# PG11__CAN_CONN.net
KiCad netlist of a schematic drawn in Altium Designer
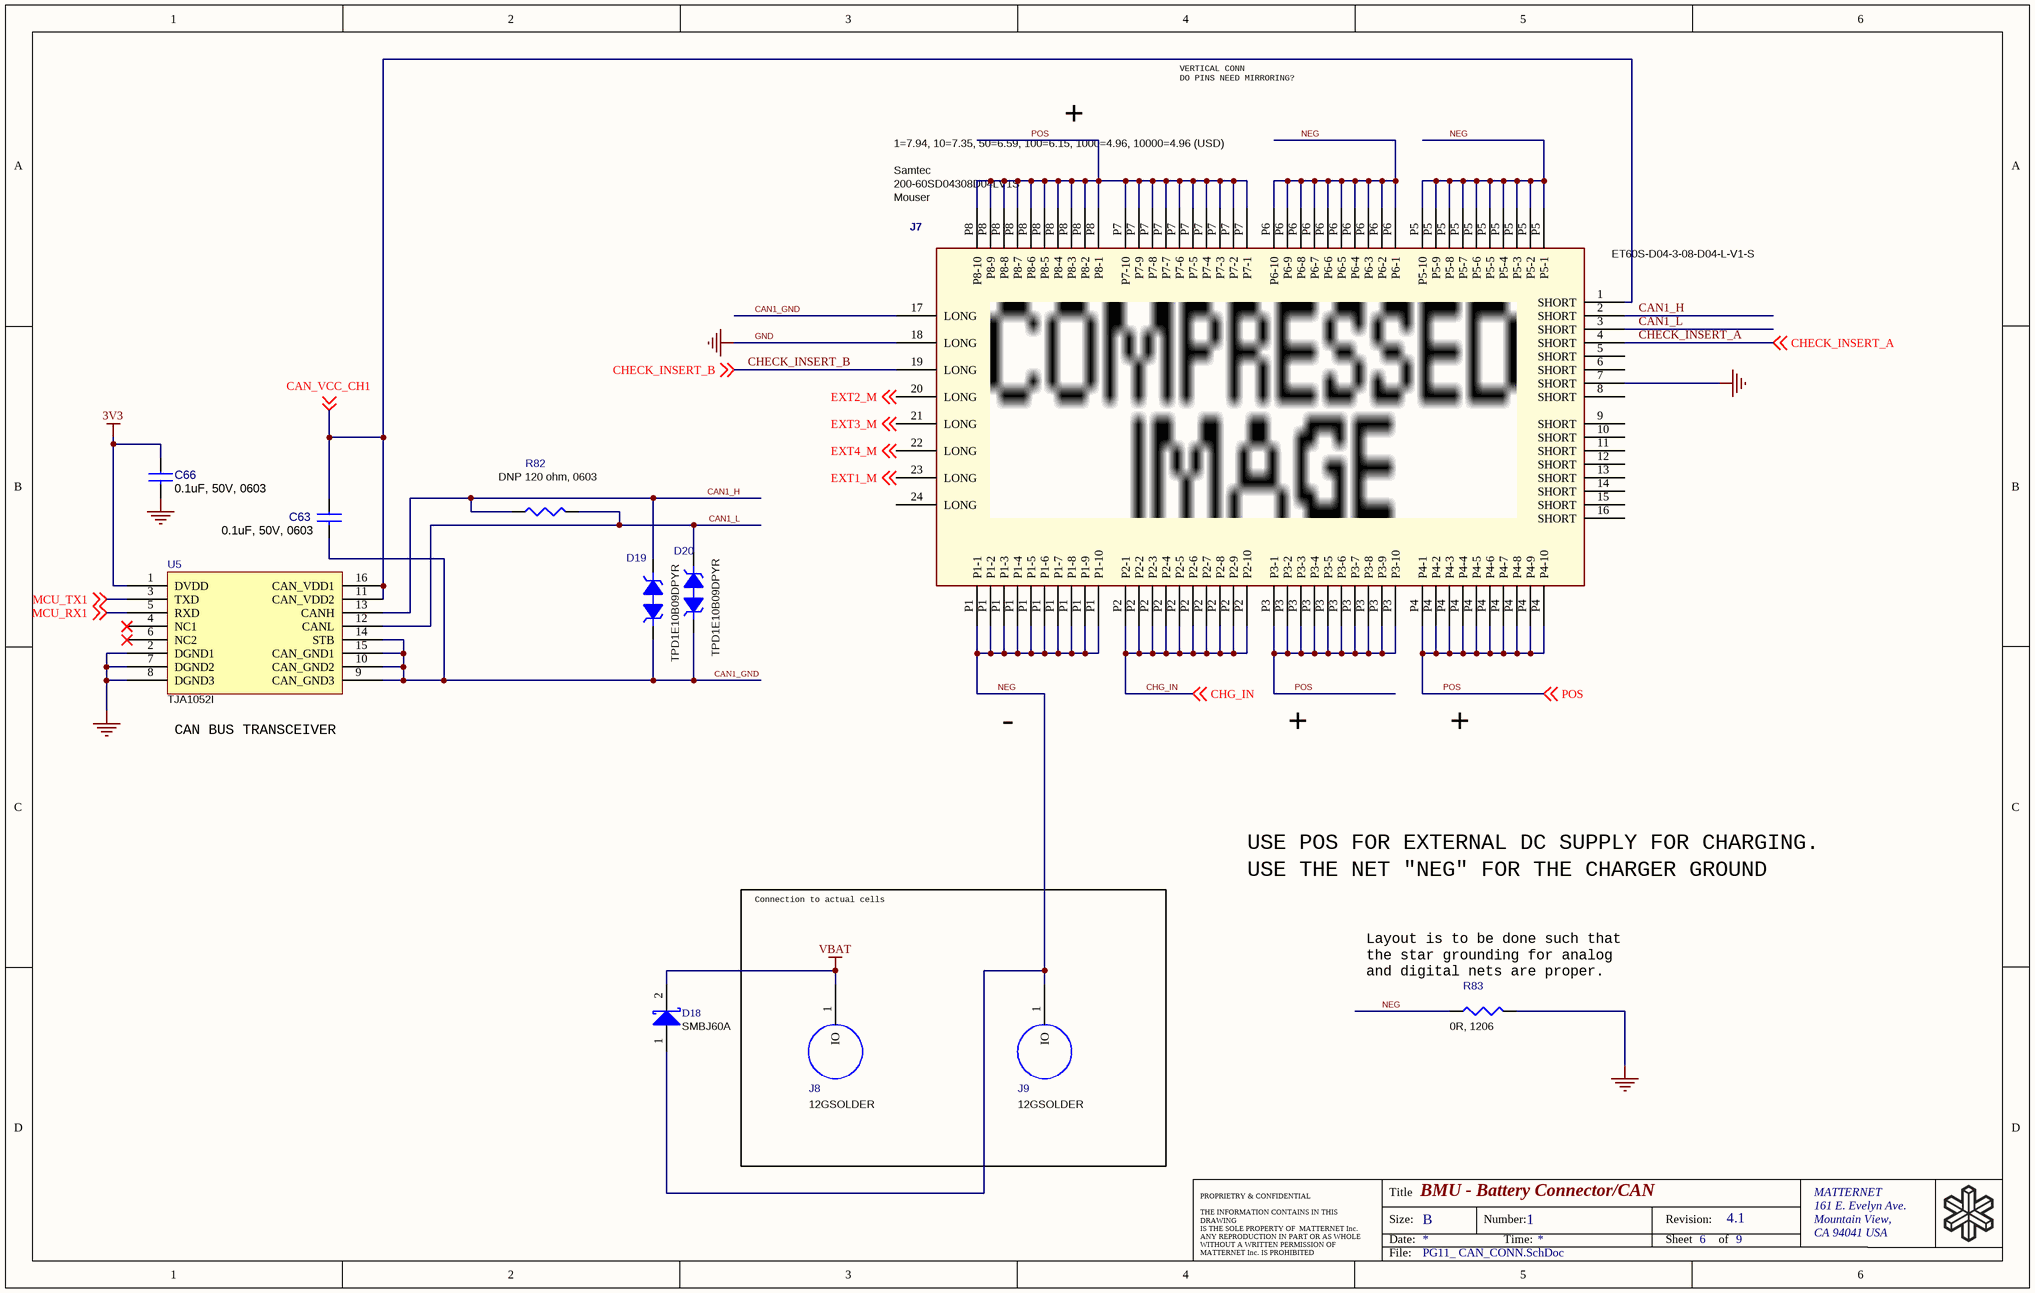
[diagram p0: PG11_ CAN_CONN.SchDoc]

(export (version "E")
  (design (tool "Eeschema 10.0.6"))
  (components
    (comp (ref "C63")
      (value "0.1uF, 50V, 0603")
      (footprint "C0603")
      (description "CAP CER 0.1UF 50V 10% X7R 0603")
      (fields
        (field (name "MANUFACTURER") "Murata")
        (field (name "MANUFACTURER PART NUMBER") "GCJ188R71E104KA12D")
      )
      (libsource (lib "*") (part "CAP-Generic-0603"))
    )
    (comp (ref "C66")
      (value "0.1uF, 50V, 0603")
      (footprint "C0603")
      (description "CAP CER 0.1UF 50V 10% X7R 0603")
      (fields
        (field (name "MANUFACTURER") "Murata")
        (field (name "MANUFACTURER PART NUMBER") "GCJ188R71E104KA12D")
      )
      (libsource (lib "*") (part "CAP-Generic-0603"))
    )
    (comp (ref "D18")
      (value "SMBJ60A")
      (footprint "DO-214AA")
      (description "ESD Suppressors / TVS Diodes 60Vr")
      (fields
        (field (name "MANUFACTURER") "Vishay Semiconductors")
        (field (name "MANUFACTURER PART NUMBER") "SMBJ60A-E3/52")
      )
      (libsource (lib "M2_V8_BMU_V1.0") (part "SMBJ60A"))
    )
    (comp (ref "D19")
      (value "TPD1E10B09DPYR")
      (footprint "2X2SON")
      (description "TVS DIODE 9VWM 20VC 2X2SON")
      (fields (field (name "MANUFACTURER") "Texas Instruments"))
      (libsource (lib "*") (part "ESD BI-DIR TRIG 9VDC 0402_0"))
    )
    (comp (ref "D20")
      (value "TPD1E10B09DPYR")
      (footprint "2X2SON")
      (description "TVS DIODE 9VWM 20VC 2X2SON")
      (fields (field (name "MANUFACTURER") "Texas Instruments"))
      (libsource (lib "*") (part "ESD BI-DIR TRIG 9VDC 0402_0"))
    )
    (comp (ref "J7")
      (value "ET60S-D04-3-08-D04-L-V1-S")
      (footprint "ET60S-D04-3-08-D04-L-V1-S")
      (description "EXtreme Ten60 Power Connector")
      (fields
        (field (name "SUPPLIER 1") "Mouser")
        (field (name "SUPPLIER PART NUMBER 1") "200-60SD04308D04LV1S")
        (field (name "MANUFACTURER") "Samtec")
        (field (name "PRICING 1") "1=7.94, 10=7.35, 50=6.59, 100=6.15, 1000=4.96, 10000=4.96 (USD)")
      )
      (libsource (lib "M2_V8_BMU_V1.0") (part "ET60S-D04-3-08-D04-L-V1-S"))
    )
    (comp (ref "J8") (value "12GSOLDER") (footprint "12GPAD") (libsource (lib "*") (part "12GSOLDER")))
    (comp (ref "J9") (value "12GSOLDER") (footprint "12GPAD") (libsource (lib "*") (part "12GSOLDER")))
    (comp (ref "R82")
      (value "DNP 120 ohm, 0603")
      (footprint "R0603")
      (libsource (lib "*") (part "R-Generic-0603"))
    )
    (comp (ref "R83")
      (value "0R, 1206")
      (footprint "R1206")
      (description "RES SMD 0 OHM JUMPER 1/4W 1206")
      (fields
        (field (name "MANUFACTURER") "Yageo")
        (field (name "MANUFACTURER PART NUMBER") "RC1206JR-070RL")
      )
      (libsource (lib "*") (part "R-Generic-1206"))
    )
    (comp (ref "U5")
      (value "TJA1052I")
      (footprint "16-SOIC")
      (description "CAN Bus, Transceiver SOIC")
      (fields
        (field (name "MANUFACTURER") "NXP Semiconductors")
        (field (name "MANUFACTURER PART NUMBER") "TJA1052IT/5Y")
      )
      (libsource (lib "M2_V8_BMU_V1.0") (part "TJA1052I"))
    )
  )
  (nets
    (net (code "1") (name "/CAN1_GND") (class "Default")
      (node (ref "C63") (pin "2") (pinfunction "2_2") (pintype "passive"))
      (node (ref "D19") (pin "1") (pinfunction "1_1") (pintype "passive"))
      (node (ref "D20") (pin "1") (pinfunction "1_1") (pintype "passive"))
      (node (ref "J7") (pin "17") (pinfunction "LONG_17") (pintype "passive"))
      (node (ref "U5") (pin "10") (pinfunction "CAN_GND2_10") (pintype "passive"))
      (node (ref "U5") (pin "14") (pinfunction "STB_14") (pintype "passive"))
      (node (ref "U5") (pin "15") (pinfunction "CAN_GND1_15") (pintype "passive"))
      (node (ref "U5") (pin "9") (pinfunction "CAN_GND3_9") (pintype "passive"))
    )
    (net (code "2") (name "/CAN1_H") (class "Default")
      (node (ref "D19") (pin "2") (pinfunction "2_2") (pintype "passive"))
      (node (ref "J7") (pin "2") (pinfunction "SHORT_2") (pintype "passive"))
      (node (ref "R82") (pin "1") (pinfunction "1_1") (pintype "passive"))
      (node (ref "U5") (pin "13") (pinfunction "CANH_13") (pintype "passive"))
    )
    (net (code "3") (name "/CAN1_L") (class "Default")
      (node (ref "D20") (pin "2") (pinfunction "2_2") (pintype "passive"))
      (node (ref "J7") (pin "3") (pinfunction "SHORT_3") (pintype "passive"))
      (node (ref "R82") (pin "2") (pinfunction "2_2") (pintype "passive"))
      (node (ref "U5") (pin "12") (pinfunction "CANL_12") (pintype "passive"))
    )
    (net (code "4") (name "/NEG") (class "Default")
      (node (ref "D18") (pin "1") (pinfunction "A_1") (pintype "passive"))
      (node (ref "J7") (pin "P1") (pinfunction "P1-6_P1") (pintype "passive"))
      (node (ref "J7") (pin "P5") (pinfunction "P5-10_P5") (pintype "passive"))
      (node (ref "J7") (pin "P6") (pinfunction "P6-1_P6") (pintype "passive"))
      (node (ref "J9") (pin "1") (pinfunction "IO_1") (pintype "passive"))
      (node (ref "R83") (pin "2") (pinfunction "2_2") (pintype "passive"))
    )
    (net (code "5") (name "3V3") (class "Default")
      (node (ref "C66") (pin "1") (pinfunction "1_1") (pintype "passive"))
      (node (ref "U5") (pin "1") (pinfunction "DVDD_1") (pintype "passive"))
    )
    (net (code "6") (name "CAN_VCC_CH1") (class "Default")
      (node (ref "C63") (pin "1") (pinfunction "1_1") (pintype "passive"))
      (node (ref "J7") (pin "1") (pinfunction "SHORT_1") (pintype "passive"))
      (node (ref "U5") (pin "11") (pinfunction "CAN_VDD2_11") (pintype "passive"))
      (node (ref "U5") (pin "16") (pinfunction "CAN_VDD1_16") (pintype "passive"))
    )
    (net (code "7") (name "CHECK_INSERT_A") (class "Default")
      (node (ref "J7") (pin "4") (pinfunction "SHORT_4") (pintype "passive"))
    )
    (net (code "8") (name "CHECK_INSERT_B") (class "Default")
      (node (ref "J7") (pin "19") (pinfunction "LONG_19") (pintype "passive"))
    )
    (net (code "9") (name "CHG_IN") (class "Default")
      (node (ref "J7") (pin "P2") (pinfunction "P2-1_P2") (pintype "passive"))
    )
    (net (code "10") (name "EXT1_M") (class "Default")
      (node (ref "J7") (pin "23") (pinfunction "LONG_23") (pintype "passive"))
    )
    (net (code "11") (name "EXT2_M") (class "Default")
      (node (ref "J7") (pin "20") (pinfunction "LONG_20") (pintype "passive"))
    )
    (net (code "12") (name "EXT3_M") (class "Default")
      (node (ref "J7") (pin "21") (pinfunction "LONG_21") (pintype "passive"))
    )
    (net (code "13") (name "EXT4_M") (class "Default")
      (node (ref "J7") (pin "22") (pinfunction "LONG_22") (pintype "passive"))
    )
    (net (code "14") (name "GND") (class "Default")
      (node (ref "C66") (pin "2") (pinfunction "2_2") (pintype "passive"))
      (node (ref "J7") (pin "18") (pinfunction "LONG_18") (pintype "passive"))
      (node (ref "J7") (pin "7") (pinfunction "SHORT_7") (pintype "passive"))
      (node (ref "R83") (pin "1") (pinfunction "1_1") (pintype "passive"))
      (node (ref "U5") (pin "2") (pinfunction "DGND1_2") (pintype "passive"))
      (node (ref "U5") (pin "7") (pinfunction "DGND2_7") (pintype "passive"))
      (node (ref "U5") (pin "8") (pinfunction "DGND3_8") (pintype "passive"))
    )
    (net (code "15") (name "MCU_RX1") (class "Default")
      (node (ref "U5") (pin "5") (pinfunction "RXD_5") (pintype "passive"))
    )
    (net (code "16") (name "MCU_TX1") (class "Default")
      (node (ref "U5") (pin "3") (pinfunction "TXD_3") (pintype "passive"))
    )
    (net (code "17") (name "POS") (class "Default")
      (node (ref "J7") (pin "P3") (pinfunction "P3-1_P3") (pintype "passive"))
      (node (ref "J7") (pin "P4") (pinfunction "P4-10_P4") (pintype "passive"))
      (node (ref "J7") (pin "P7") (pinfunction "P7-3_P7") (pintype "passive"))
      (node (ref "J7") (pin "P8") (pinfunction "P8-10_P8") (pintype "passive"))
    )
    (net (code "18") (name "VBAT") (class "Default")
      (node (ref "D18") (pin "2") (pinfunction "K_2") (pintype "passive"))
      (node (ref "J8") (pin "1") (pinfunction "IO_1") (pintype "passive"))
    )
    (net (code "19") (name "unconnected-(J7-LONG-Pad24)") (class "Default")
      (node (ref "J7") (pin "24") (pinfunction "LONG_24") (pintype "passive"))
    )
    (net (code "20") (name "unconnected-(J7-SHORT-Pad5)") (class "Default")
      (node (ref "J7") (pin "5") (pinfunction "SHORT_5") (pintype "passive"))
    )
    (net (code "21") (name "unconnected-(J7-SHORT-Pad6)") (class "Default")
      (node (ref "J7") (pin "6") (pinfunction "SHORT_6") (pintype "passive"))
    )
    (net (code "22") (name "unconnected-(J7-SHORT-Pad8)") (class "Default")
      (node (ref "J7") (pin "8") (pinfunction "SHORT_8") (pintype "passive"))
    )
    (net (code "23") (name "unconnected-(J7-SHORT-Pad9)") (class "Default")
      (node (ref "J7") (pin "9") (pinfunction "SHORT_9") (pintype "passive"))
    )
    (net (code "24") (name "unconnected-(J7-SHORT-Pad10)") (class "Default")
      (node (ref "J7") (pin "10") (pinfunction "SHORT_10") (pintype "passive"))
    )
    (net (code "25") (name "unconnected-(J7-SHORT-Pad11)") (class "Default")
      (node (ref "J7") (pin "11") (pinfunction "SHORT_11") (pintype "passive"))
    )
    (net (code "26") (name "unconnected-(J7-SHORT-Pad12)") (class "Default")
      (node (ref "J7") (pin "12") (pinfunction "SHORT_12") (pintype "passive"))
    )
    (net (code "27") (name "unconnected-(J7-SHORT-Pad13)") (class "Default")
      (node (ref "J7") (pin "13") (pinfunction "SHORT_13") (pintype "passive"))
    )
    (net (code "28") (name "unconnected-(J7-SHORT-Pad14)") (class "Default")
      (node (ref "J7") (pin "14") (pinfunction "SHORT_14") (pintype "passive"))
    )
    (net (code "29") (name "unconnected-(J7-SHORT-Pad15)") (class "Default")
      (node (ref "J7") (pin "15") (pinfunction "SHORT_15") (pintype "passive"))
    )
    (net (code "30") (name "unconnected-(J7-SHORT-Pad16)") (class "Default")
      (node (ref "J7") (pin "16") (pinfunction "SHORT_16") (pintype "passive"))
    )
    (net (code "31") (name "unconnected-(U5-NC1-Pad4)") (class "Default")
      (node (ref "U5") (pin "4") (pinfunction "NC1_4") (pintype "passive+no_connect"))
    )
    (net (code "32") (name "unconnected-(U5-NC2-Pad6)") (class "Default")
      (node (ref "U5") (pin "6") (pinfunction "NC2_6") (pintype "passive+no_connect"))
    )
  )
)
